# Pump.net
KiCad netlist of a schematic drawn in Altium Designer
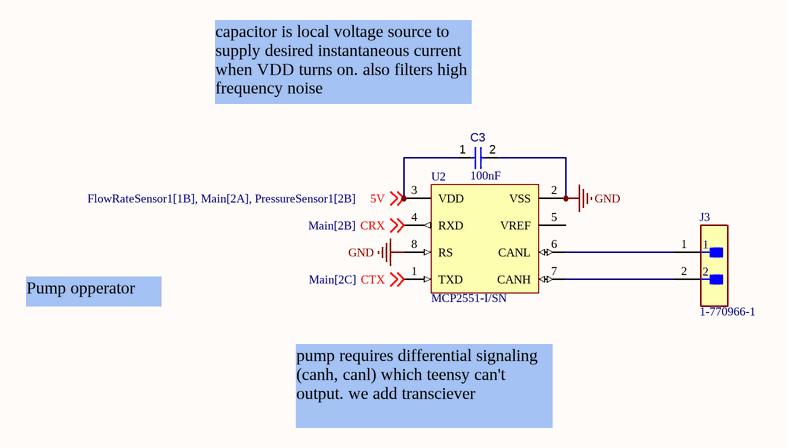
[diagram p0: Pump.SchDoc]

(export (version "E")
  (design (tool "Eeschema 10.0.6"))
  (components
    (comp (ref "C3")
      (value "100nF")
      (footprint "CAPC1005X56X25LL10T15")
      (description "Chip Capacitor, 0.1 uF, +/- 5%, 16 V, 0402 (1005 Metric)")
      (fields (field (name "TOLERANCE") "5%") (field (name "Comment") "Capacitor 0.1 uF +/- 5% 16 V 0402"))
      (libsource (lib "Alt_ium Course") (part "CAP-NP-2"))
    )
    (comp (ref "J3")
      (value "1-770966-1")
      (footprint "FP-1-770966-1-MFG")
      (description "CONN HEADER R/A 2POS 4.14MM")
      (fields
        (field (name "OCTOPART") "https://octopart.com/1-770966-1-te+connectivity-46506767")
        (field (name "MANUFACTURER") "TE")
      )
      (libsource (lib "Altium Content Vault") (part "3bc925449376181038e59eaffc5286c"))
    )
    (comp (ref "U2")
      (value "MCP2551-I/SN")
      (footprint "MCHP-SN8_V")
      (fields (field (name "MANUFACTURER") "Microchip"))
      (libsource (lib "Altium Content Vault") (part "MCHP-MCP2551-SN8"))
    )
  )
  (nets
    (net (code "1") (name "5V") (class "Default")
      (node (ref "C3") (pin "1") (pinfunction "1_1") (pintype "passive"))
      (node (ref "U2") (pin "3") (pinfunction "VDD_3") (pintype "power_in"))
    )
    (net (code "2") (name "CRX") (class "Default")
      (node (ref "U2") (pin "4") (pinfunction "RXD_4") (pintype "output"))
    )
    (net (code "3") (name "CTX") (class "Default")
      (node (ref "U2") (pin "1") (pinfunction "TXD_1") (pintype "input"))
    )
    (net (code "4") (name "GND") (class "Default")
      (node (ref "C3") (pin "2") (pinfunction "2_2") (pintype "passive"))
      (node (ref "U2") (pin "2") (pinfunction "VSS_2") (pintype "power_in"))
      (node (ref "U2") (pin "8") (pinfunction "RS_8") (pintype "input"))
    )
    (net (code "5") (name "Net-(U2-CANH)") (class "Default")
      (node (ref "J3") (pin "2") (pinfunction "2_2") (pintype "passive"))
      (node (ref "U2") (pin "7") (pinfunction "CANH_7") (pintype "bidirectional"))
    )
    (net (code "6") (name "Net-(U2-CANL)") (class "Default")
      (node (ref "J3") (pin "1") (pinfunction "1_1") (pintype "passive"))
      (node (ref "U2") (pin "6") (pinfunction "CANL_6") (pintype "bidirectional"))
    )
    (net (code "7") (name "unconnected-(U2-VREF-Pad5)") (class "Default")
      (node (ref "U2") (pin "5") (pinfunction "VREF_5") (pintype "power_in"))
    )
  )
)
